# Clock_v2_1.net
KiCad netlist of a schematic drawn in EAGLE
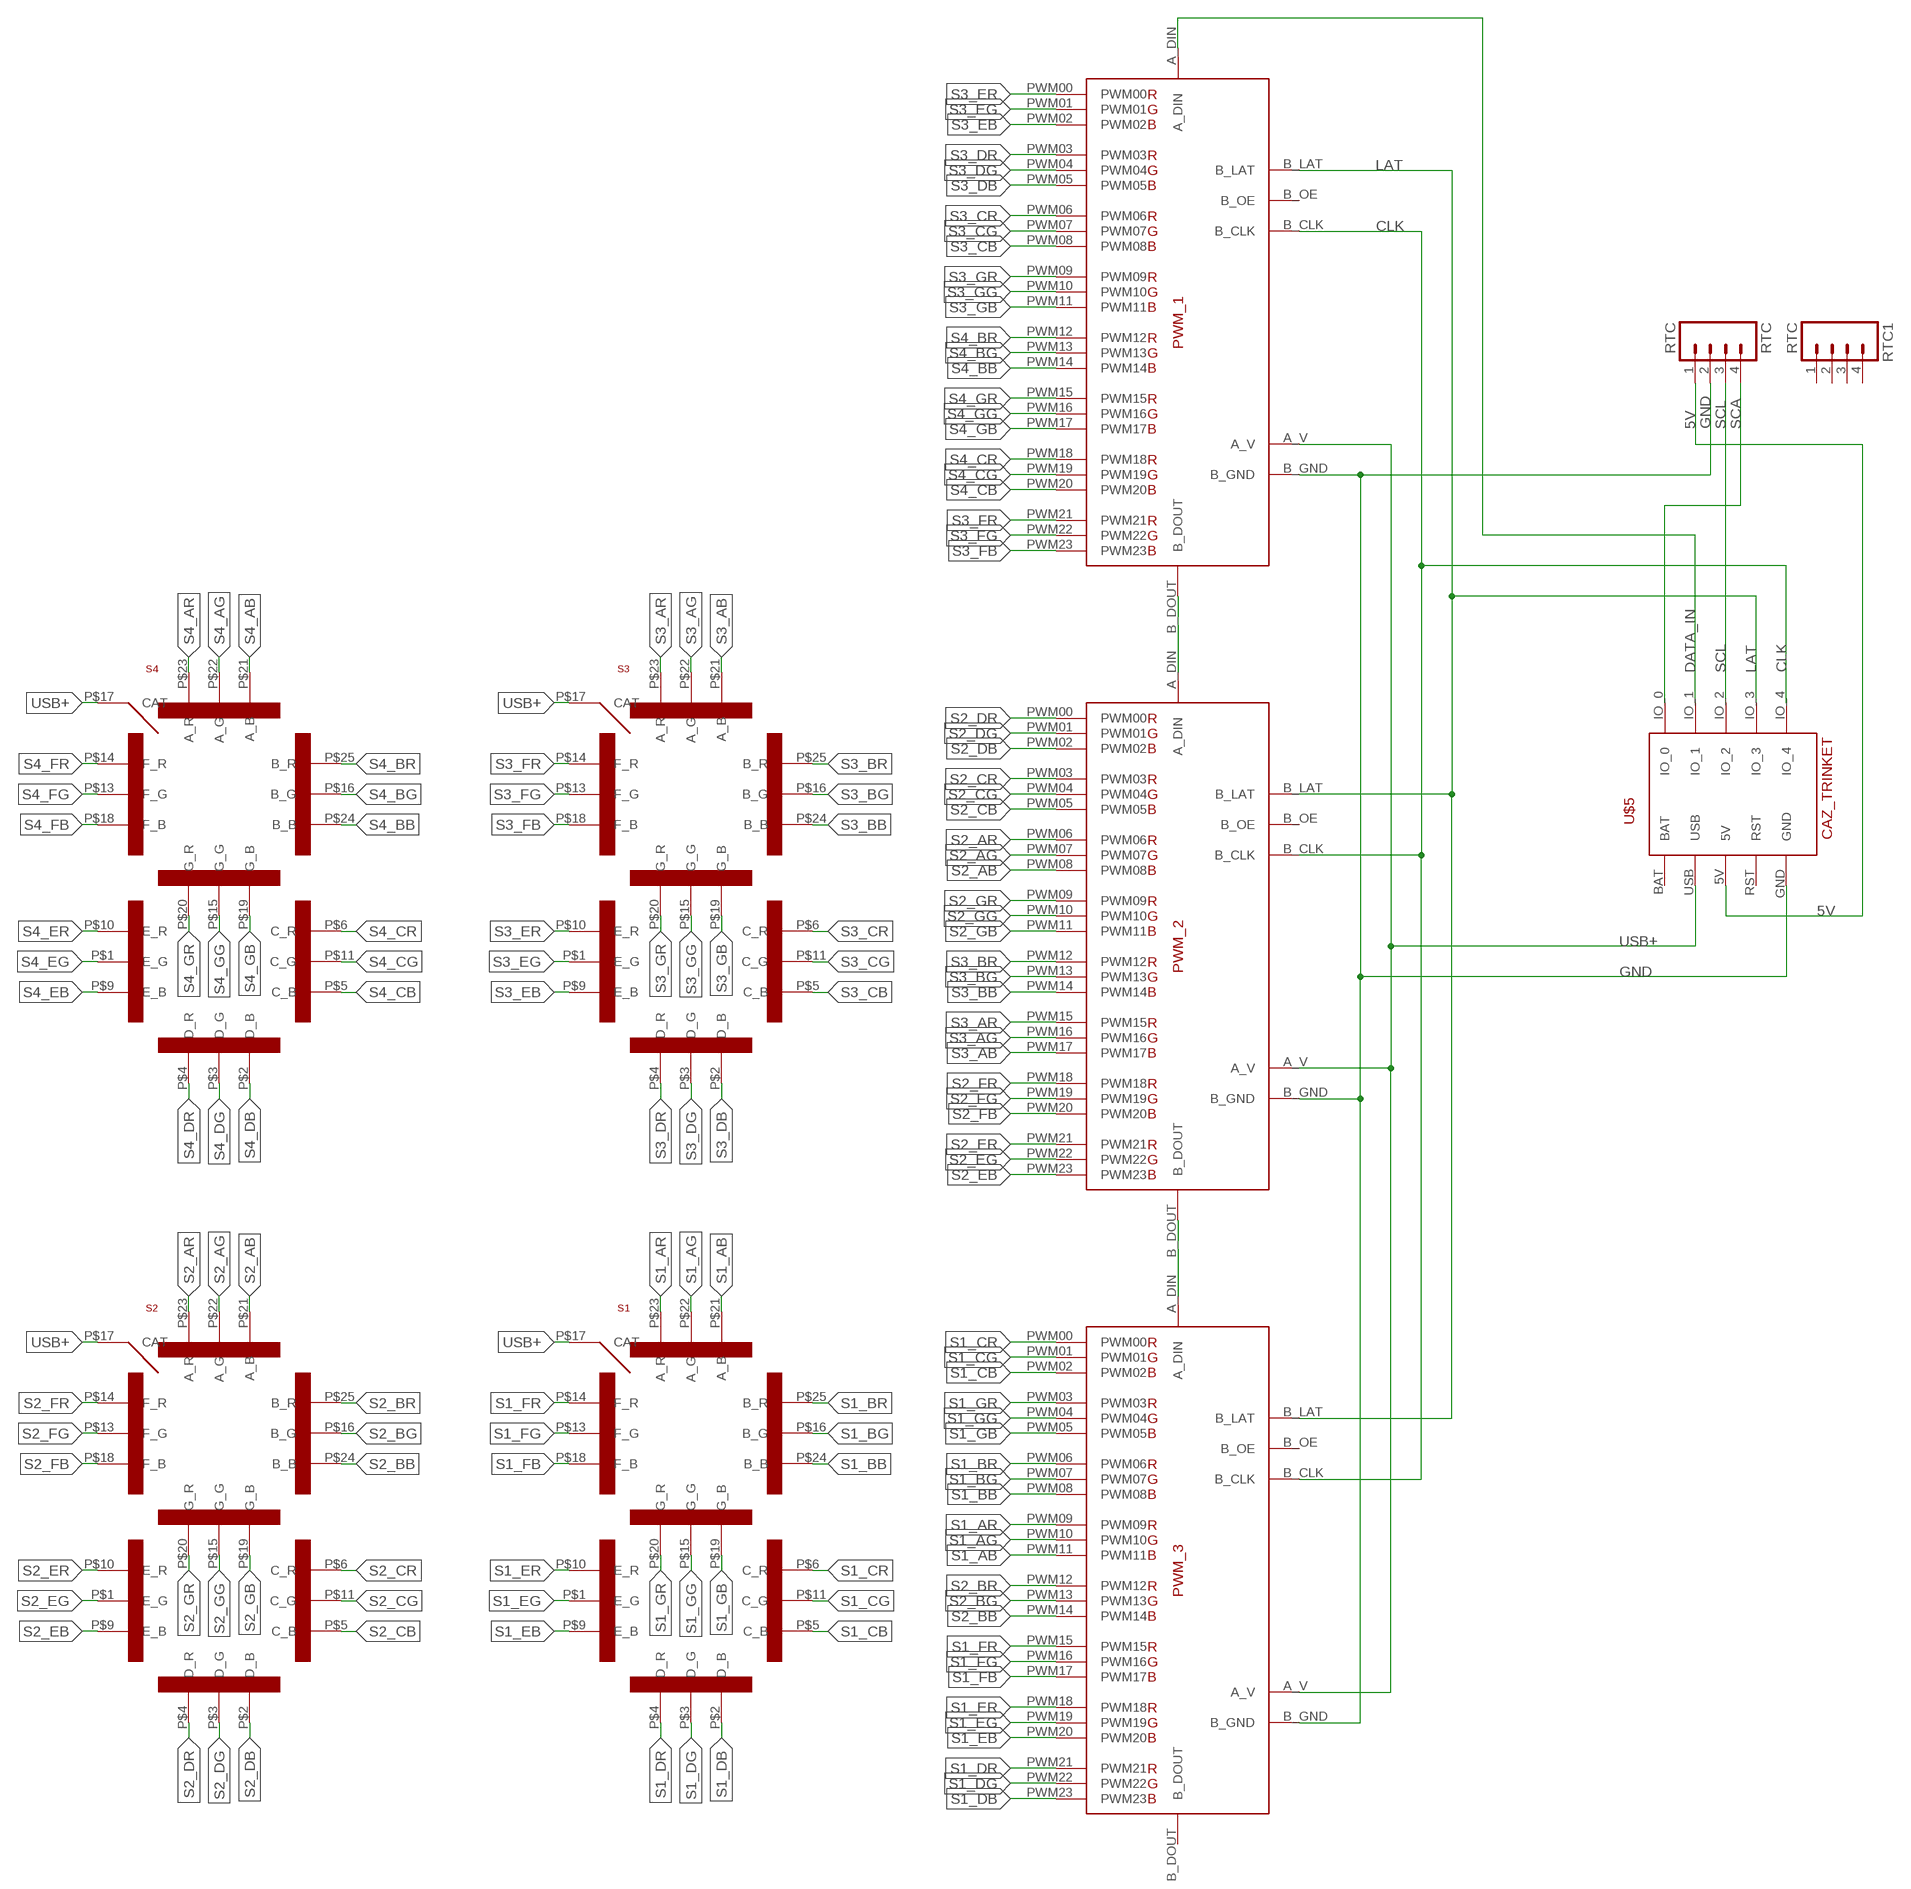
[diagram p0: schematic, sheet 1]

(export (version "E")
  (design (tool "Eeschema 10.0.6"))
  (components
    (comp (ref "PWM_1")
      (value "CAZ_24PWM_DRIVER_MINIMAL")
      (footprint "eagle-import:CAZ_24PWM_DRIVER_MINIMAL")
      (libsource (lib "eagle-import") (part "CAZ_24PWM_DRIVER_MINIMAL"))
    )
    (comp (ref "PWM_2")
      (value "CAZ_24PWM_DRIVER_MINIMAL")
      (footprint "eagle-import:CAZ_24PWM_DRIVER_MINIMAL")
      (libsource (lib "eagle-import") (part "CAZ_24PWM_DRIVER_MINIMAL"))
    )
    (comp (ref "PWM_3")
      (value "CAZ_24PWM_DRIVER_MINIMAL")
      (footprint "eagle-import:CAZ_24PWM_DRIVER_MINIMAL")
      (libsource (lib "eagle-import") (part "CAZ_24PWM_DRIVER_MINIMAL"))
    )
    (comp (ref "RTC")
      (value "RTC")
      (footprint "eagle-import:1X04_NO_SILK")
      (libsource (lib "eagle-import") (part "M041X04_NO_SILK"))
    )
    (comp (ref "RTC1")
      (value "RTC")
      (footprint "eagle-import:1X04_NO_SILK")
      (libsource (lib "eagle-import") (part "M041X04_NO_SILK"))
    )
    (comp (ref "S1")
      (value "CAZ_7SEGMENT_RGB_LEDBACKSIDE_MOUNT")
      (footprint "eagle-import:CAZ_7SEGMENT_RGB_LED")
      (fields (field (name "CREATED_BY") "caz"))
      (libsource (lib "eagle-import") (part "CAZ_7SEGMENT_RGB_LEDBACKSIDE_MOUNT"))
    )
    (comp (ref "S2")
      (value "CAZ_7SEGMENT_RGB_LEDBACKSIDE_MOUNT")
      (footprint "eagle-import:CAZ_7SEGMENT_RGB_LED")
      (fields (field (name "CREATED_BY") "caz"))
      (libsource (lib "eagle-import") (part "CAZ_7SEGMENT_RGB_LEDBACKSIDE_MOUNT"))
    )
    (comp (ref "S3")
      (value "CAZ_7SEGMENT_RGB_LEDBACKSIDE_MOUNT")
      (footprint "eagle-import:CAZ_7SEGMENT_RGB_LED")
      (fields (field (name "CREATED_BY") "caz"))
      (libsource (lib "eagle-import") (part "CAZ_7SEGMENT_RGB_LEDBACKSIDE_MOUNT"))
    )
    (comp (ref "S4")
      (value "CAZ_7SEGMENT_RGB_LEDBACKSIDE_MOUNT")
      (footprint "eagle-import:CAZ_7SEGMENT_RGB_LED")
      (fields (field (name "CREATED_BY") "caz"))
      (libsource (lib "eagle-import") (part "CAZ_7SEGMENT_RGB_LEDBACKSIDE_MOUNT"))
    )
    (comp (ref "U$5")
      (value "CAZ_TRINKET")
      (footprint "eagle-import:CAZ_TRINKET")
      (libsource (lib "eagle-import") (part "CAZ_TRINKET"))
    )
  )
  (nets
    (net (code "1") (name "/5V") (class "Default")
      (node (ref "RTC") (pin "1") (pinfunction "1_1") (pintype "passive"))
      (node (ref "U$5") (pin "5V") (pinfunction "5V_5V") (pintype "bidirectional"))
    )
    (net (code "2") (name "/CLK") (class "Default")
      (node (ref "PWM_1") (pin "B_CLK") (pinfunction "B_CLK_B_CLK") (pintype "bidirectional"))
      (node (ref "PWM_2") (pin "B_CLK") (pinfunction "B_CLK_B_CLK") (pintype "bidirectional"))
      (node (ref "PWM_3") (pin "B_CLK") (pinfunction "B_CLK_B_CLK") (pintype "bidirectional"))
      (node (ref "U$5") (pin "IO_4") (pinfunction "IO_4_IO_4") (pintype "bidirectional"))
    )
    (net (code "3") (name "/DATA_IN") (class "Default")
      (node (ref "PWM_1") (pin "A_DIN") (pinfunction "A_DIN_A_DIN") (pintype "bidirectional"))
      (node (ref "U$5") (pin "IO_1") (pinfunction "IO_1_IO_1") (pintype "bidirectional"))
    )
    (net (code "4") (name "/GND") (class "Default")
      (node (ref "PWM_1") (pin "B_GND") (pinfunction "B_GND_B_GND") (pintype "bidirectional"))
      (node (ref "PWM_2") (pin "B_GND") (pinfunction "B_GND_B_GND") (pintype "bidirectional"))
      (node (ref "PWM_3") (pin "B_GND") (pinfunction "B_GND_B_GND") (pintype "bidirectional"))
      (node (ref "RTC") (pin "2") (pinfunction "2_2") (pintype "passive"))
      (node (ref "U$5") (pin "GND") (pinfunction "GND_GND") (pintype "bidirectional"))
    )
    (net (code "5") (name "/LAT") (class "Default")
      (node (ref "PWM_1") (pin "B_LAT") (pinfunction "B_LAT_B_LAT") (pintype "bidirectional"))
      (node (ref "PWM_2") (pin "B_LAT") (pinfunction "B_LAT_B_LAT") (pintype "bidirectional"))
      (node (ref "PWM_3") (pin "B_LAT") (pinfunction "B_LAT_B_LAT") (pintype "bidirectional"))
      (node (ref "U$5") (pin "IO_3") (pinfunction "IO_3_IO_3") (pintype "bidirectional"))
    )
    (net (code "6") (name "/SCA") (class "Default")
      (node (ref "RTC") (pin "4") (pinfunction "4_4") (pintype "passive"))
      (node (ref "U$5") (pin "IO_0") (pinfunction "IO_0_IO_0") (pintype "bidirectional"))
    )
    (net (code "7") (name "/SCL") (class "Default")
      (node (ref "RTC") (pin "3") (pinfunction "3_3") (pintype "passive"))
      (node (ref "U$5") (pin "IO_2") (pinfunction "IO_2_IO_2") (pintype "bidirectional"))
    )
    (net (code "8") (name "Net-(PWM_1-PadB_DOUT)") (class "Default")
      (node (ref "PWM_1") (pin "B_DOUT") (pinfunction "B_DOUT_B_DOUT") (pintype "bidirectional"))
      (node (ref "PWM_2") (pin "A_DIN") (pinfunction "A_DIN_A_DIN") (pintype "bidirectional"))
    )
    (net (code "9") (name "Net-(PWM_2-PadB_DOUT)") (class "Default")
      (node (ref "PWM_2") (pin "B_DOUT") (pinfunction "B_DOUT_B_DOUT") (pintype "bidirectional"))
      (node (ref "PWM_3") (pin "A_DIN") (pinfunction "A_DIN_A_DIN") (pintype "bidirectional"))
    )
    (net (code "10") (name "S1_AB") (class "Default")
      (node (ref "PWM_3") (pin "PWM11") (pinfunction "PWM11_PWM11") (pintype "bidirectional"))
      (node (ref "S1") (pin "P$21") (pinfunction "A_B_P$21") (pintype "bidirectional"))
    )
    (net (code "11") (name "S1_AG") (class "Default")
      (node (ref "PWM_3") (pin "PWM10") (pinfunction "PWM10_PWM10") (pintype "bidirectional"))
      (node (ref "S1") (pin "P$22") (pinfunction "A_G_P$22") (pintype "bidirectional"))
    )
    (net (code "12") (name "S1_AR") (class "Default")
      (node (ref "PWM_3") (pin "PWM09") (pinfunction "PWM09_PWM09") (pintype "bidirectional"))
      (node (ref "S1") (pin "P$23") (pinfunction "A_R_P$23") (pintype "bidirectional"))
    )
    (net (code "13") (name "S1_BB") (class "Default")
      (node (ref "PWM_3") (pin "PWM08") (pinfunction "PWM08_PWM08") (pintype "bidirectional"))
      (node (ref "S1") (pin "P$24") (pinfunction "B_B_P$24") (pintype "bidirectional"))
    )
    (net (code "14") (name "S1_BG") (class "Default")
      (node (ref "PWM_3") (pin "PWM07") (pinfunction "PWM07_PWM07") (pintype "bidirectional"))
      (node (ref "S1") (pin "P$16") (pinfunction "B_G_P$16") (pintype "bidirectional"))
    )
    (net (code "15") (name "S1_BR") (class "Default")
      (node (ref "PWM_3") (pin "PWM06") (pinfunction "PWM06_PWM06") (pintype "bidirectional"))
      (node (ref "S1") (pin "P$25") (pinfunction "B_R_P$25") (pintype "bidirectional"))
    )
    (net (code "16") (name "S1_CB") (class "Default")
      (node (ref "PWM_3") (pin "PWM02") (pinfunction "PWM02_PWM02") (pintype "bidirectional"))
      (node (ref "S1") (pin "P$5") (pinfunction "C_B_P$5") (pintype "bidirectional"))
    )
    (net (code "17") (name "S1_CG") (class "Default")
      (node (ref "PWM_3") (pin "PWM01") (pinfunction "PWM01_PWM01") (pintype "bidirectional"))
      (node (ref "S1") (pin "P$11") (pinfunction "C_G_P$11") (pintype "bidirectional"))
    )
    (net (code "18") (name "S1_CR") (class "Default")
      (node (ref "PWM_3") (pin "PWM00") (pinfunction "PWM00_PWM00") (pintype "bidirectional"))
      (node (ref "S1") (pin "P$6") (pinfunction "C_R_P$6") (pintype "bidirectional"))
    )
    (net (code "19") (name "S1_DB") (class "Default")
      (node (ref "PWM_3") (pin "PWM23") (pinfunction "PWM23_PWM23") (pintype "bidirectional"))
      (node (ref "S1") (pin "P$2") (pinfunction "D_B_P$2") (pintype "bidirectional"))
    )
    (net (code "20") (name "S1_DG") (class "Default")
      (node (ref "PWM_3") (pin "PWM22") (pinfunction "PWM22_PWM22") (pintype "bidirectional"))
      (node (ref "S1") (pin "P$3") (pinfunction "D_G_P$3") (pintype "bidirectional"))
    )
    (net (code "21") (name "S1_DR") (class "Default")
      (node (ref "PWM_3") (pin "PWM21") (pinfunction "PWM21_PWM21") (pintype "bidirectional"))
      (node (ref "S1") (pin "P$4") (pinfunction "D_R_P$4") (pintype "bidirectional"))
    )
    (net (code "22") (name "S1_EB") (class "Default")
      (node (ref "PWM_3") (pin "PWM20") (pinfunction "PWM20_PWM20") (pintype "bidirectional"))
      (node (ref "S1") (pin "P$9") (pinfunction "E_B_P$9") (pintype "bidirectional"))
    )
    (net (code "23") (name "S1_EG") (class "Default")
      (node (ref "PWM_3") (pin "PWM19") (pinfunction "PWM19_PWM19") (pintype "bidirectional"))
      (node (ref "S1") (pin "P$1") (pinfunction "E_G_P$1") (pintype "bidirectional"))
    )
    (net (code "24") (name "S1_ER") (class "Default")
      (node (ref "PWM_3") (pin "PWM18") (pinfunction "PWM18_PWM18") (pintype "bidirectional"))
      (node (ref "S1") (pin "P$10") (pinfunction "E_R_P$10") (pintype "bidirectional"))
    )
    (net (code "25") (name "S1_FB") (class "Default")
      (node (ref "PWM_3") (pin "PWM17") (pinfunction "PWM17_PWM17") (pintype "bidirectional"))
      (node (ref "S1") (pin "P$18") (pinfunction "F_B_P$18") (pintype "bidirectional"))
    )
    (net (code "26") (name "S1_FG") (class "Default")
      (node (ref "PWM_3") (pin "PWM16") (pinfunction "PWM16_PWM16") (pintype "bidirectional"))
      (node (ref "S1") (pin "P$13") (pinfunction "F_G_P$13") (pintype "bidirectional"))
    )
    (net (code "27") (name "S1_FR") (class "Default")
      (node (ref "PWM_3") (pin "PWM15") (pinfunction "PWM15_PWM15") (pintype "bidirectional"))
      (node (ref "S1") (pin "P$14") (pinfunction "F_R_P$14") (pintype "bidirectional"))
    )
    (net (code "28") (name "S1_GB") (class "Default")
      (node (ref "PWM_3") (pin "PWM05") (pinfunction "PWM05_PWM05") (pintype "bidirectional"))
      (node (ref "S1") (pin "P$19") (pinfunction "G_B_P$19") (pintype "bidirectional"))
    )
    (net (code "29") (name "S1_GG") (class "Default")
      (node (ref "PWM_3") (pin "PWM04") (pinfunction "PWM04_PWM04") (pintype "bidirectional"))
      (node (ref "S1") (pin "P$15") (pinfunction "G_G_P$15") (pintype "bidirectional"))
    )
    (net (code "30") (name "S1_GR") (class "Default")
      (node (ref "PWM_3") (pin "PWM03") (pinfunction "PWM03_PWM03") (pintype "bidirectional"))
      (node (ref "S1") (pin "P$20") (pinfunction "G_R_P$20") (pintype "bidirectional"))
    )
    (net (code "31") (name "S2_AB") (class "Default")
      (node (ref "PWM_2") (pin "PWM08") (pinfunction "PWM08_PWM08") (pintype "bidirectional"))
      (node (ref "S2") (pin "P$21") (pinfunction "A_B_P$21") (pintype "bidirectional"))
    )
    (net (code "32") (name "S2_AG") (class "Default")
      (node (ref "PWM_2") (pin "PWM07") (pinfunction "PWM07_PWM07") (pintype "bidirectional"))
      (node (ref "S2") (pin "P$22") (pinfunction "A_G_P$22") (pintype "bidirectional"))
    )
    (net (code "33") (name "S2_AR") (class "Default")
      (node (ref "PWM_2") (pin "PWM06") (pinfunction "PWM06_PWM06") (pintype "bidirectional"))
      (node (ref "S2") (pin "P$23") (pinfunction "A_R_P$23") (pintype "bidirectional"))
    )
    (net (code "34") (name "S2_BB") (class "Default")
      (node (ref "PWM_3") (pin "PWM14") (pinfunction "PWM14_PWM14") (pintype "bidirectional"))
      (node (ref "S2") (pin "P$24") (pinfunction "B_B_P$24") (pintype "bidirectional"))
    )
    (net (code "35") (name "S2_BG") (class "Default")
      (node (ref "PWM_3") (pin "PWM13") (pinfunction "PWM13_PWM13") (pintype "bidirectional"))
      (node (ref "S2") (pin "P$16") (pinfunction "B_G_P$16") (pintype "bidirectional"))
    )
    (net (code "36") (name "S2_BR") (class "Default")
      (node (ref "PWM_3") (pin "PWM12") (pinfunction "PWM12_PWM12") (pintype "bidirectional"))
      (node (ref "S2") (pin "P$25") (pinfunction "B_R_P$25") (pintype "bidirectional"))
    )
    (net (code "37") (name "S2_CB") (class "Default")
      (node (ref "PWM_2") (pin "PWM05") (pinfunction "PWM05_PWM05") (pintype "bidirectional"))
      (node (ref "S2") (pin "P$5") (pinfunction "C_B_P$5") (pintype "bidirectional"))
    )
    (net (code "38") (name "S2_CG") (class "Default")
      (node (ref "PWM_2") (pin "PWM04") (pinfunction "PWM04_PWM04") (pintype "bidirectional"))
      (node (ref "S2") (pin "P$11") (pinfunction "C_G_P$11") (pintype "bidirectional"))
    )
    (net (code "39") (name "S2_CR") (class "Default")
      (node (ref "PWM_2") (pin "PWM03") (pinfunction "PWM03_PWM03") (pintype "bidirectional"))
      (node (ref "S2") (pin "P$6") (pinfunction "C_R_P$6") (pintype "bidirectional"))
    )
    (net (code "40") (name "S2_DB") (class "Default")
      (node (ref "PWM_2") (pin "PWM02") (pinfunction "PWM02_PWM02") (pintype "bidirectional"))
      (node (ref "S2") (pin "P$2") (pinfunction "D_B_P$2") (pintype "bidirectional"))
    )
    (net (code "41") (name "S2_DG") (class "Default")
      (node (ref "PWM_2") (pin "PWM01") (pinfunction "PWM01_PWM01") (pintype "bidirectional"))
      (node (ref "S2") (pin "P$3") (pinfunction "D_G_P$3") (pintype "bidirectional"))
    )
    (net (code "42") (name "S2_DR") (class "Default")
      (node (ref "PWM_2") (pin "PWM00") (pinfunction "PWM00_PWM00") (pintype "bidirectional"))
      (node (ref "S2") (pin "P$4") (pinfunction "D_R_P$4") (pintype "bidirectional"))
    )
    (net (code "43") (name "S2_EB") (class "Default")
      (node (ref "PWM_2") (pin "PWM23") (pinfunction "PWM23_PWM23") (pintype "bidirectional"))
      (node (ref "S2") (pin "P$9") (pinfunction "E_B_P$9") (pintype "bidirectional"))
    )
    (net (code "44") (name "S2_EG") (class "Default")
      (node (ref "PWM_2") (pin "PWM22") (pinfunction "PWM22_PWM22") (pintype "bidirectional"))
      (node (ref "S2") (pin "P$1") (pinfunction "E_G_P$1") (pintype "bidirectional"))
    )
    (net (code "45") (name "S2_ER") (class "Default")
      (node (ref "PWM_2") (pin "PWM21") (pinfunction "PWM21_PWM21") (pintype "bidirectional"))
      (node (ref "S2") (pin "P$10") (pinfunction "E_R_P$10") (pintype "bidirectional"))
    )
    (net (code "46") (name "S2_FB") (class "Default")
      (node (ref "PWM_2") (pin "PWM20") (pinfunction "PWM20_PWM20") (pintype "bidirectional"))
      (node (ref "S2") (pin "P$18") (pinfunction "F_B_P$18") (pintype "bidirectional"))
    )
    (net (code "47") (name "S2_FG") (class "Default")
      (node (ref "PWM_2") (pin "PWM19") (pinfunction "PWM19_PWM19") (pintype "bidirectional"))
      (node (ref "S2") (pin "P$13") (pinfunction "F_G_P$13") (pintype "bidirectional"))
    )
    (net (code "48") (name "S2_FR") (class "Default")
      (node (ref "PWM_2") (pin "PWM18") (pinfunction "PWM18_PWM18") (pintype "bidirectional"))
      (node (ref "S2") (pin "P$14") (pinfunction "F_R_P$14") (pintype "bidirectional"))
    )
    (net (code "49") (name "S2_GB") (class "Default")
      (node (ref "PWM_2") (pin "PWM11") (pinfunction "PWM11_PWM11") (pintype "bidirectional"))
      (node (ref "S2") (pin "P$19") (pinfunction "G_B_P$19") (pintype "bidirectional"))
    )
    (net (code "50") (name "S2_GG") (class "Default")
      (node (ref "PWM_2") (pin "PWM10") (pinfunction "PWM10_PWM10") (pintype "bidirectional"))
      (node (ref "S2") (pin "P$15") (pinfunction "G_G_P$15") (pintype "bidirectional"))
    )
    (net (code "51") (name "S2_GR") (class "Default")
      (node (ref "PWM_2") (pin "PWM09") (pinfunction "PWM09_PWM09") (pintype "bidirectional"))
      (node (ref "S2") (pin "P$20") (pinfunction "G_R_P$20") (pintype "bidirectional"))
    )
    (net (code "52") (name "S3_AB") (class "Default")
      (node (ref "PWM_2") (pin "PWM17") (pinfunction "PWM17_PWM17") (pintype "bidirectional"))
      (node (ref "S3") (pin "P$21") (pinfunction "A_B_P$21") (pintype "bidirectional"))
    )
    (net (code "53") (name "S3_AG") (class "Default")
      (node (ref "PWM_2") (pin "PWM16") (pinfunction "PWM16_PWM16") (pintype "bidirectional"))
      (node (ref "S3") (pin "P$22") (pinfunction "A_G_P$22") (pintype "bidirectional"))
    )
    (net (code "54") (name "S3_AR") (class "Default")
      (node (ref "PWM_2") (pin "PWM15") (pinfunction "PWM15_PWM15") (pintype "bidirectional"))
      (node (ref "S3") (pin "P$23") (pinfunction "A_R_P$23") (pintype "bidirectional"))
    )
    (net (code "55") (name "S3_BB") (class "Default")
      (node (ref "PWM_2") (pin "PWM14") (pinfunction "PWM14_PWM14") (pintype "bidirectional"))
      (node (ref "S3") (pin "P$24") (pinfunction "B_B_P$24") (pintype "bidirectional"))
    )
    (net (code "56") (name "S3_BG") (class "Default")
      (node (ref "PWM_2") (pin "PWM13") (pinfunction "PWM13_PWM13") (pintype "bidirectional"))
      (node (ref "S3") (pin "P$16") (pinfunction "B_G_P$16") (pintype "bidirectional"))
    )
    (net (code "57") (name "S3_BR") (class "Default")
      (node (ref "PWM_2") (pin "PWM12") (pinfunction "PWM12_PWM12") (pintype "bidirectional"))
      (node (ref "S3") (pin "P$25") (pinfunction "B_R_P$25") (pintype "bidirectional"))
    )
    (net (code "58") (name "S3_CB") (class "Default")
      (node (ref "PWM_1") (pin "PWM08") (pinfunction "PWM08_PWM08") (pintype "bidirectional"))
      (node (ref "S3") (pin "P$5") (pinfunction "C_B_P$5") (pintype "bidirectional"))
    )
    (net (code "59") (name "S3_CG") (class "Default")
      (node (ref "PWM_1") (pin "PWM07") (pinfunction "PWM07_PWM07") (pintype "bidirectional"))
      (node (ref "S3") (pin "P$11") (pinfunction "C_G_P$11") (pintype "bidirectional"))
    )
    (net (code "60") (name "S3_CR") (class "Default")
      (node (ref "PWM_1") (pin "PWM06") (pinfunction "PWM06_PWM06") (pintype "bidirectional"))
      (node (ref "S3") (pin "P$6") (pinfunction "C_R_P$6") (pintype "bidirectional"))
    )
    (net (code "61") (name "S3_DB") (class "Default")
      (node (ref "PWM_1") (pin "PWM05") (pinfunction "PWM05_PWM05") (pintype "bidirectional"))
      (node (ref "S3") (pin "P$2") (pinfunction "D_B_P$2") (pintype "bidirectional"))
    )
    (net (code "62") (name "S3_DG") (class "Default")
      (node (ref "PWM_1") (pin "PWM04") (pinfunction "PWM04_PWM04") (pintype "bidirectional"))
      (node (ref "S3") (pin "P$3") (pinfunction "D_G_P$3") (pintype "bidirectional"))
    )
    (net (code "63") (name "S3_DR") (class "Default")
      (node (ref "PWM_1") (pin "PWM03") (pinfunction "PWM03_PWM03") (pintype "bidirectional"))
      (node (ref "S3") (pin "P$4") (pinfunction "D_R_P$4") (pintype "bidirectional"))
    )
    (net (code "64") (name "S3_EB") (class "Default")
      (node (ref "PWM_1") (pin "PWM02") (pinfunction "PWM02_PWM02") (pintype "bidirectional"))
      (node (ref "S3") (pin "P$9") (pinfunction "E_B_P$9") (pintype "bidirectional"))
    )
    (net (code "65") (name "S3_EG") (class "Default")
      (node (ref "PWM_1") (pin "PWM01") (pinfunction "PWM01_PWM01") (pintype "bidirectional"))
      (node (ref "S3") (pin "P$1") (pinfunction "E_G_P$1") (pintype "bidirectional"))
    )
    (net (code "66") (name "S3_ER") (class "Default")
      (node (ref "PWM_1") (pin "PWM00") (pinfunction "PWM00_PWM00") (pintype "bidirectional"))
      (node (ref "S3") (pin "P$10") (pinfunction "E_R_P$10") (pintype "bidirectional"))
    )
    (net (code "67") (name "S3_FB") (class "Default")
      (node (ref "PWM_1") (pin "PWM23") (pinfunction "PWM23_PWM23") (pintype "bidirectional"))
      (node (ref "S3") (pin "P$18") (pinfunction "F_B_P$18") (pintype "bidirectional"))
    )
    (net (code "68") (name "S3_FG") (class "Default")
      (node (ref "PWM_1") (pin "PWM22") (pinfunction "PWM22_PWM22") (pintype "bidirectional"))
      (node (ref "S3") (pin "P$13") (pinfunction "F_G_P$13") (pintype "bidirectional"))
    )
    (net (code "69") (name "S3_FR") (class "Default")
      (node (ref "PWM_1") (pin "PWM21") (pinfunction "PWM21_PWM21") (pintype "bidirectional"))
      (node (ref "S3") (pin "P$14") (pinfunction "F_R_P$14") (pintype "bidirectional"))
    )
    (net (code "70") (name "S3_GB") (class "Default")
      (node (ref "PWM_1") (pin "PWM11") (pinfunction "PWM11_PWM11") (pintype "bidirectional"))
      (node (ref "S3") (pin "P$19") (pinfunction "G_B_P$19") (pintype "bidirectional"))
    )
    (net (code "71") (name "S3_GG") (class "Default")
      (node (ref "PWM_1") (pin "PWM10") (pinfunction "PWM10_PWM10") (pintype "bidirectional"))
      (node (ref "S3") (pin "P$15") (pinfunction "G_G_P$15") (pintype "bidirectional"))
    )
    (net (code "72") (name "S3_GR") (class "Default")
      (node (ref "PWM_1") (pin "PWM09") (pinfunction "PWM09_PWM09") (pintype "bidirectional"))
      (node (ref "S3") (pin "P$20") (pinfunction "G_R_P$20") (pintype "bidirectional"))
    )
    (net (code "73") (name "S4_AB") (class "Default")
      (node (ref "S4") (pin "P$21") (pinfunction "A_B_P$21") (pintype "bidirectional"))
    )
    (net (code "74") (name "S4_AG") (class "Default")
      (node (ref "S4") (pin "P$22") (pinfunction "A_G_P$22") (pintype "bidirectional"))
    )
    (net (code "75") (name "S4_AR") (class "Default")
      (node (ref "S4") (pin "P$23") (pinfunction "A_R_P$23") (pintype "bidirectional"))
    )
    (net (code "76") (name "S4_BB") (class "Default")
      (node (ref "PWM_1") (pin "PWM14") (pinfunction "PWM14_PWM14") (pintype "bidirectional"))
      (node (ref "S4") (pin "P$24") (pinfunction "B_B_P$24") (pintype "bidirectional"))
    )
    (net (code "77") (name "S4_BG") (class "Default")
      (node (ref "PWM_1") (pin "PWM13") (pinfunction "PWM13_PWM13") (pintype "bidirectional"))
      (node (ref "S4") (pin "P$16") (pinfunction "B_G_P$16") (pintype "bidirectional"))
    )
    (net (code "78") (name "S4_BR") (class "Default")
      (node (ref "PWM_1") (pin "PWM12") (pinfunction "PWM12_PWM12") (pintype "bidirectional"))
      (node (ref "S4") (pin "P$25") (pinfunction "B_R_P$25") (pintype "bidirectional"))
    )
    (net (code "79") (name "S4_CB") (class "Default")
      (node (ref "PWM_1") (pin "PWM20") (pinfunction "PWM20_PWM20") (pintype "bidirectional"))
      (node (ref "S4") (pin "P$5") (pinfunction "C_B_P$5") (pintype "bidirectional"))
    )
    (net (code "80") (name "S4_CG") (class "Default")
      (node (ref "PWM_1") (pin "PWM19") (pinfunction "PWM19_PWM19") (pintype "bidirectional"))
      (node (ref "S4") (pin "P$11") (pinfunction "C_G_P$11") (pintype "bidirectional"))
    )
    (net (code "81") (name "S4_CR") (class "Default")
      (node (ref "PWM_1") (pin "PWM18") (pinfunction "PWM18_PWM18") (pintype "bidirectional"))
      (node (ref "S4") (pin "P$6") (pinfunction "C_R_P$6") (pintype "bidirectional"))
    )
    (net (code "82") (name "S4_DB") (class "Default")
      (node (ref "S4") (pin "P$2") (pinfunction "D_B_P$2") (pintype "bidirectional"))
    )
    (net (code "83") (name "S4_DG") (class "Default")
      (node (ref "S4") (pin "P$3") (pinfunction "D_G_P$3") (pintype "bidirectional"))
    )
    (net (code "84") (name "S4_DR") (class "Default")
      (node (ref "S4") (pin "P$4") (pinfunction "D_R_P$4") (pintype "bidirectional"))
    )
    (net (code "85") (name "S4_EB") (class "Default")
      (node (ref "S4") (pin "P$9") (pinfunction "E_B_P$9") (pintype "bidirectional"))
    )
    (net (code "86") (name "S4_EG") (class "Default")
      (node (ref "S4") (pin "P$1") (pinfunction "E_G_P$1") (pintype "bidirectional"))
    )
    (net (code "87") (name "S4_ER") (class "Default")
      (node (ref "S4") (pin "P$10") (pinfunction "E_R_P$10") (pintype "bidirectional"))
    )
    (net (code "88") (name "S4_FB") (class "Default")
      (node (ref "S4") (pin "P$18") (pinfunction "F_B_P$18") (pintype "bidirectional"))
    )
    (net (code "89") (name "S4_FG") (class "Default")
      (node (ref "S4") (pin "P$13") (pinfunction "F_G_P$13") (pintype "bidirectional"))
    )
    (net (code "90") (name "S4_FR") (class "Default")
      (node (ref "S4") (pin "P$14") (pinfunction "F_R_P$14") (pintype "bidirectional"))
    )
    (net (code "91") (name "S4_GB") (class "Default")
      (node (ref "PWM_1") (pin "PWM17") (pinfunction "PWM17_PWM17") (pintype "bidirectional"))
      (node (ref "S4") (pin "P$19") (pinfunction "G_B_P$19") (pintype "bidirectional"))
    )
    (net (code "92") (name "S4_GG") (class "Default")
      (node (ref "PWM_1") (pin "PWM16") (pinfunction "PWM16_PWM16") (pintype "bidirectional"))
      (node (ref "S4") (pin "P$15") (pinfunction "G_G_P$15") (pintype "bidirectional"))
    )
    (net (code "93") (name "S4_GR") (class "Default")
      (node (ref "PWM_1") (pin "PWM15") (pinfunction "PWM15_PWM15") (pintype "bidirectional"))
      (node (ref "S4") (pin "P$20") (pinfunction "G_R_P$20") (pintype "bidirectional"))
    )
    (net (code "94") (name "USB+") (class "Default")
      (node (ref "PWM_1") (pin "A_V") (pinfunction "A_V_A_V") (pintype "bidirectional"))
      (node (ref "PWM_2") (pin "A_V") (pinfunction "A_V_A_V") (pintype "bidirectional"))
      (node (ref "PWM_3") (pin "A_V") (pinfunction "A_V_A_V") (pintype "bidirectional"))
      (node (ref "S1") (pin "P$17") (pinfunction "CAT_P$17") (pintype "bidirectional"))
      (node (ref "S2") (pin "P$17") (pinfunction "CAT_P$17") (pintype "bidirectional"))
      (node (ref "S3") (pin "P$17") (pinfunction "CAT_P$17") (pintype "bidirectional"))
      (node (ref "S4") (pin "P$17") (pinfunction "CAT_P$17") (pintype "bidirectional"))
      (node (ref "U$5") (pin "USB") (pinfunction "USB_USB") (pintype "bidirectional"))
    )
    (net (code "95") (name "unconnected-(PWM_1-PadB_OE)") (class "Default")
      (node (ref "PWM_1") (pin "B_OE") (pinfunction "B_OE_B_OE") (pintype "bidirectional"))
    )
    (net (code "96") (name "unconnected-(PWM_2-PadB_OE)") (class "Default")
      (node (ref "PWM_2") (pin "B_OE") (pinfunction "B_OE_B_OE") (pintype "bidirectional"))
    )
    (net (code "97") (name "unconnected-(PWM_3-PadB_DOUT)") (class "Default")
      (node (ref "PWM_3") (pin "B_DOUT") (pinfunction "B_DOUT_B_DOUT") (pintype "bidirectional"))
    )
    (net (code "98") (name "unconnected-(PWM_3-PadB_OE)") (class "Default")
      (node (ref "PWM_3") (pin "B_OE") (pinfunction "B_OE_B_OE") (pintype "bidirectional"))
    )
    (net (code "99") (name "unconnected-(RTC1-Pad1)") (class "Default")
      (node (ref "RTC1") (pin "1") (pinfunction "1_1") (pintype "passive"))
    )
    (net (code "100") (name "unconnected-(RTC1-Pad2)") (class "Default")
      (node (ref "RTC1") (pin "2") (pinfunction "2_2") (pintype "passive"))
    )
    (net (code "101") (name "unconnected-(RTC1-Pad3)") (class "Default")
      (node (ref "RTC1") (pin "3") (pinfunction "3_3") (pintype "passive"))
    )
    (net (code "102") (name "unconnected-(RTC1-Pad4)") (class "Default")
      (node (ref "RTC1") (pin "4") (pinfunction "4_4") (pintype "passive"))
    )
    (net (code "103") (name "unconnected-(U$5-PadBAT)") (class "Default")
      (node (ref "U$5") (pin "BAT") (pinfunction "BAT_BAT") (pintype "bidirectional"))
    )
    (net (code "104") (name "unconnected-(U$5-PadRST)") (class "Default")
      (node (ref "U$5") (pin "RST") (pinfunction "RST_RST") (pintype "bidirectional"))
    )
  )
)
